# wchasp_v3.net
KiCad netlist of a schematic drawn in EAGLE
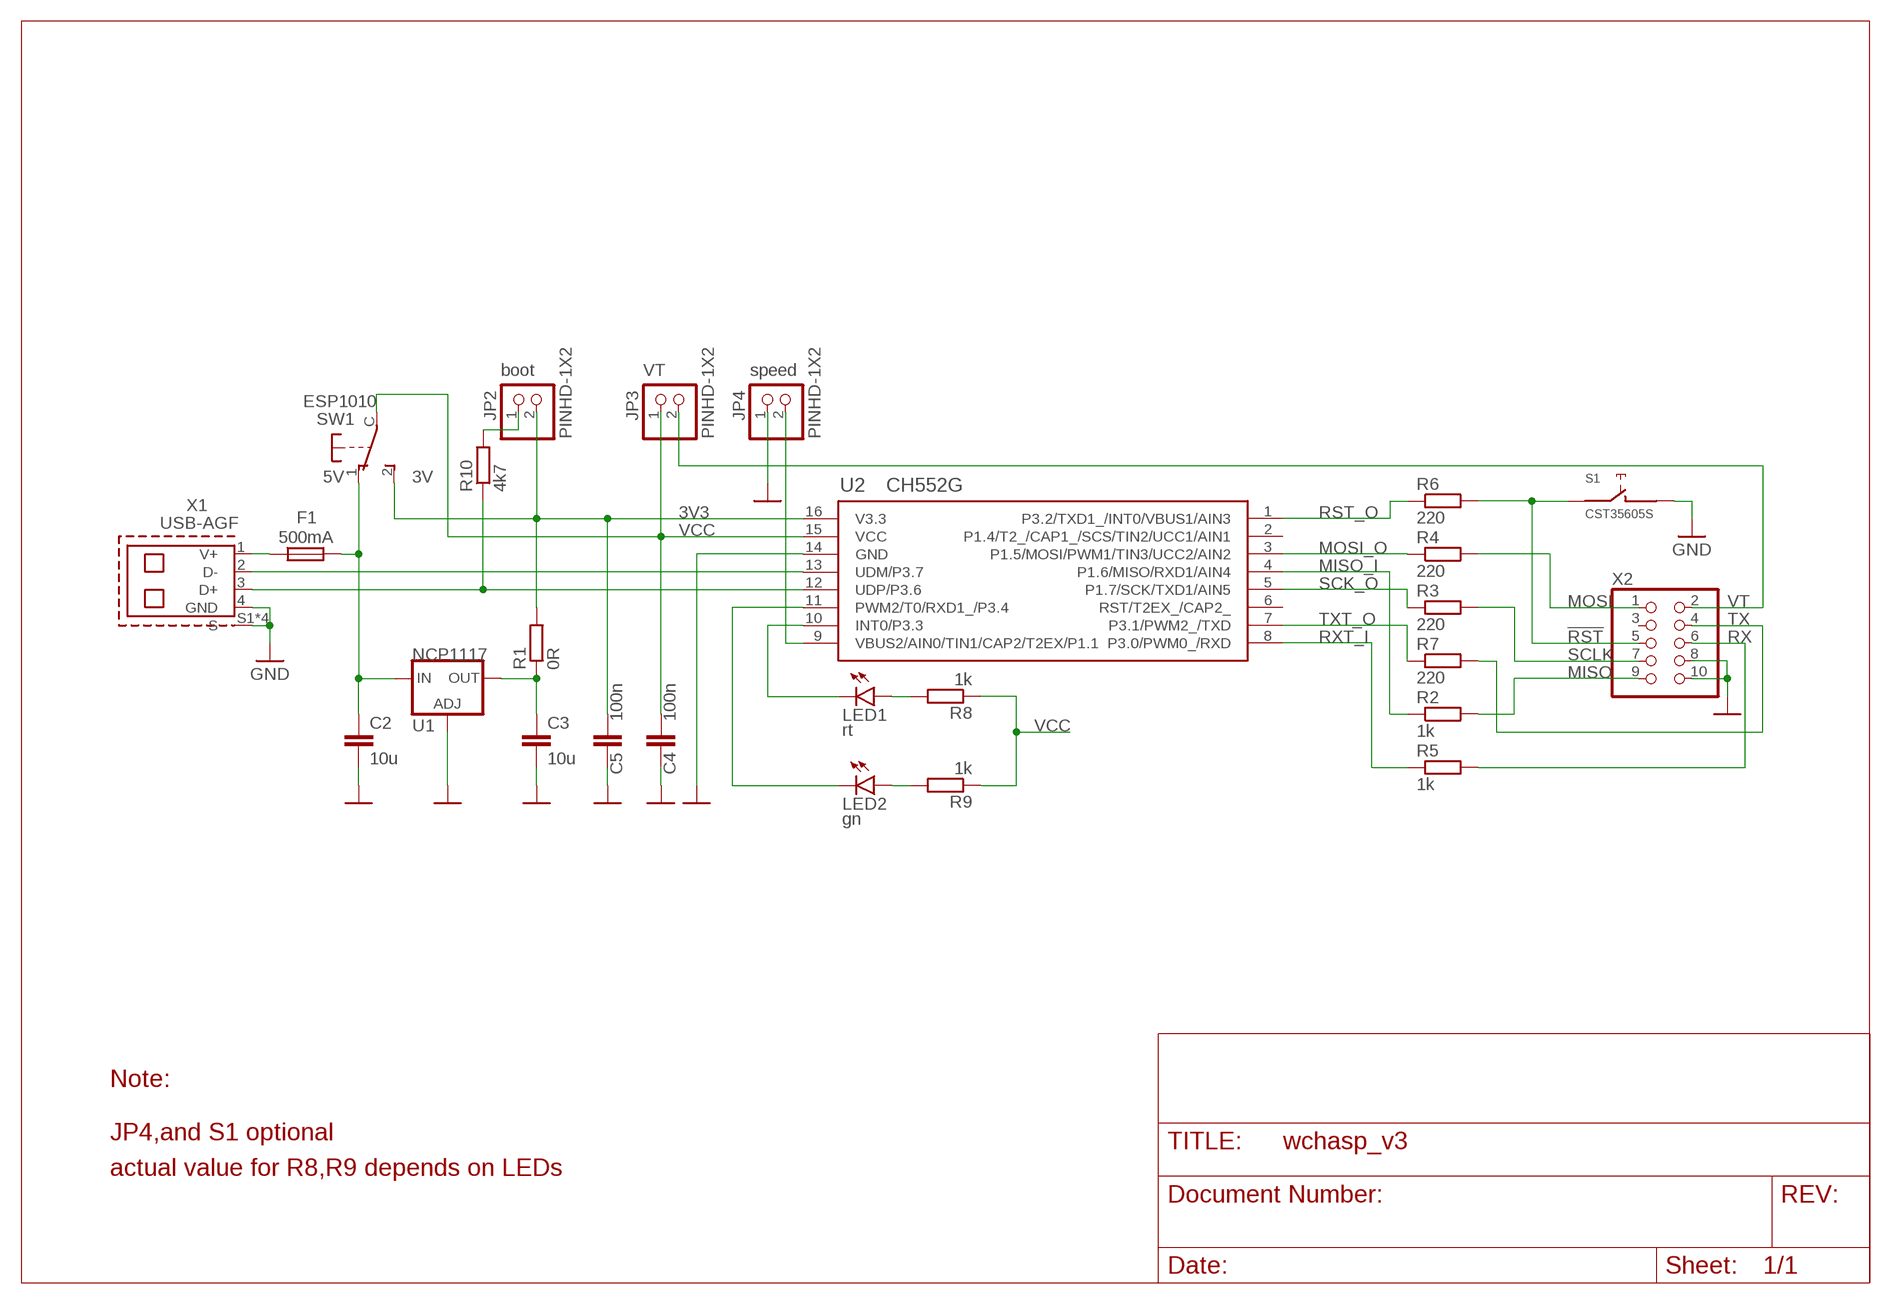
[diagram p0: schematic, sheet 1]

(export (version "E")
  (design (tool "Eeschema 10.0.6"))
  (components
    (comp (ref "C2")
      (value "10u")
      (footprint "eagle-import:C0805K")
      (libsource (lib "eagle-import") (part "C-EUC0805K"))
    )
    (comp (ref "C3")
      (value "10u")
      (footprint "eagle-import:C0805K")
      (libsource (lib "eagle-import") (part "C-EUC0805K"))
    )
    (comp (ref "C4")
      (value "100n")
      (footprint "eagle-import:C0603")
      (libsource (lib "eagle-import") (part "C-EUC0603"))
    )
    (comp (ref "C5")
      (value "100n")
      (footprint "eagle-import:C0603")
      (libsource (lib "eagle-import") (part "C-EUC0603"))
    )
    (comp (ref "F1")
      (value "500mA")
      (footprint "eagle-import:R0805W")
      (libsource (lib "eagle-import") (part "R-EU_R0805W"))
    )
    (comp (ref "JP2")
      (value "PINHD-1X2")
      (footprint "eagle-import:1X2")
      (libsource (lib "eagle-import") (part "PINHD-1X2"))
    )
    (comp (ref "JP3")
      (value "PINHD-1X2")
      (footprint "eagle-import:1X2")
      (libsource (lib "eagle-import") (part "PINHD-1X2"))
    )
    (comp (ref "JP4")
      (value "PINHD-1X2")
      (footprint "eagle-import:1X2")
      (libsource (lib "eagle-import") (part "PINHD-1X2"))
    )
    (comp (ref "LED1")
      (value "rt")
      (footprint "eagle-import:D0603")
      (libsource (lib "eagle-import") (part "LED_0603"))
    )
    (comp (ref "LED2")
      (value "gn")
      (footprint "eagle-import:D0603")
      (libsource (lib "eagle-import") (part "LED_0603"))
    )
    (comp (ref "R1")
      (value "0R")
      (footprint "eagle-import:R0603")
      (libsource (lib "eagle-import") (part "R-EU_R0603"))
    )
    (comp (ref "R2")
      (value "1k")
      (footprint "eagle-import:R0603")
      (libsource (lib "eagle-import") (part "R-EU_R0603"))
    )
    (comp (ref "R3")
      (value "220")
      (footprint "eagle-import:R0603")
      (libsource (lib "eagle-import") (part "R-EU_R0603"))
    )
    (comp (ref "R4")
      (value "220")
      (footprint "eagle-import:R0603")
      (libsource (lib "eagle-import") (part "R-EU_R0603"))
    )
    (comp (ref "R5")
      (value "1k")
      (footprint "eagle-import:R0603")
      (libsource (lib "eagle-import") (part "R-EU_R0603"))
    )
    (comp (ref "R6")
      (value "220")
      (footprint "eagle-import:R0603")
      (libsource (lib "eagle-import") (part "R-EU_R0603"))
    )
    (comp (ref "R7")
      (value "220")
      (footprint "eagle-import:R0603")
      (libsource (lib "eagle-import") (part "R-EU_R0603"))
    )
    (comp (ref "R8")
      (value "1k")
      (footprint "eagle-import:R0603")
      (libsource (lib "eagle-import") (part "R-EU_R0603"))
    )
    (comp (ref "R9")
      (value "1k")
      (footprint "eagle-import:R0603")
      (libsource (lib "eagle-import") (part "R-EU_R0603"))
    )
    (comp (ref "R10")
      (value "4k7")
      (footprint "eagle-import:R0603")
      (libsource (lib "eagle-import") (part "R-EU_R0603"))
    )
    (comp (ref "S1")
      (value "CST35605S")
      (footprint "eagle-import:CST35605S")
      (libsource (lib "eagle-import") (part "CST35605S"))
    )
    (comp (ref "SW1")
      (value "ESP1010")
      (footprint "eagle-import:ESP1010")
      (libsource (lib "eagle-import") (part "ESP1010"))
    )
    (comp (ref "U1")
      (value "NCP1117")
      (footprint "eagle-import:SOT223")
      (libsource (lib "eagle-import") (part "NCP1117"))
    )
    (comp (ref "U2")
      (value "CH552G")
      (footprint "eagle-import:SO16")
      (libsource (lib "eagle-import") (part "CH552G"))
    )
    (comp (ref "X1")
      (value "USB-AGF")
      (footprint "eagle-import:USB-AGF")
      (libsource (lib "eagle-import") (part "USB-AGF"))
    )
    (comp (ref "X2")
      (value "PINHD-2X5/90")
      (footprint "eagle-import:2X05_90")
      (libsource (lib "eagle-import") (part "PINHD-2X5/90"))
    )
  )
  (nets
    (net (code "1") (name "/3V3") (class "Default")
      (node (ref "C5") (pin "1") (pinfunction "1_1") (pintype "passive"))
      (node (ref "JP2") (pin "2") (pinfunction "2_2") (pintype "passive"))
      (node (ref "R1") (pin "2") (pinfunction "2_2") (pintype "passive"))
      (node (ref "SW1") (pin "2") (pinfunction "S_2") (pintype "passive"))
      (node (ref "U2") (pin "16") (pinfunction "V3.3_16") (pintype "output"))
    )
    (net (code "2") (name "/MISO") (class "Default")
      (node (ref "R2") (pin "2") (pinfunction "2_2") (pintype "passive"))
      (node (ref "X2") (pin "9") (pinfunction "9_9") (pintype "passive"))
    )
    (net (code "3") (name "/MISO_I") (class "Default")
      (node (ref "R2") (pin "1") (pinfunction "1_1") (pintype "passive"))
      (node (ref "U2") (pin "4") (pinfunction "P1.6/MISO/RXD1/AIN4_4") (pintype "bidirectional"))
    )
    (net (code "4") (name "/MOSI") (class "Default")
      (node (ref "R4") (pin "2") (pinfunction "2_2") (pintype "passive"))
      (node (ref "X2") (pin "1") (pinfunction "1_1") (pintype "passive"))
    )
    (net (code "5") (name "/MOSI_O") (class "Default")
      (node (ref "R4") (pin "1") (pinfunction "1_1") (pintype "passive"))
      (node (ref "U2") (pin "3") (pinfunction "P1.5/MOSI/PWM1/TIN3/UCC2/AIN2_3") (pintype "bidirectional"))
    )
    (net (code "6") (name "/RST_O") (class "Default")
      (node (ref "R6") (pin "1") (pinfunction "1_1") (pintype "passive"))
      (node (ref "U2") (pin "1") (pinfunction "P3.2/TXD1_/INT0/VBUS1/AIN3_1") (pintype "bidirectional"))
    )
    (net (code "7") (name "/RX") (class "Default")
      (node (ref "R5") (pin "2") (pinfunction "2_2") (pintype "passive"))
      (node (ref "X2") (pin "6") (pinfunction "6_6") (pintype "passive"))
    )
    (net (code "8") (name "/RXT_I") (class "Default")
      (node (ref "R5") (pin "1") (pinfunction "1_1") (pintype "passive"))
      (node (ref "U2") (pin "8") (pinfunction "P3.0/PWM0_/RXD_8") (pintype "bidirectional"))
    )
    (net (code "9") (name "/SCK_O") (class "Default")
      (node (ref "R3") (pin "1") (pinfunction "1_1") (pintype "passive"))
      (node (ref "U2") (pin "5") (pinfunction "P1.7/SCK/TXD1/AIN5_5") (pintype "bidirectional"))
    )
    (net (code "10") (name "/SCLK") (class "Default")
      (node (ref "R3") (pin "2") (pinfunction "2_2") (pintype "passive"))
      (node (ref "X2") (pin "7") (pinfunction "7_7") (pintype "passive"))
    )
    (net (code "11") (name "/TX") (class "Default")
      (node (ref "R7") (pin "2") (pinfunction "2_2") (pintype "passive"))
      (node (ref "X2") (pin "4") (pinfunction "4_4") (pintype "passive"))
    )
    (net (code "12") (name "/TXT_O") (class "Default")
      (node (ref "R7") (pin "1") (pinfunction "1_1") (pintype "passive"))
      (node (ref "U2") (pin "7") (pinfunction "P3.1/PWM2_/TXD_7") (pintype "bidirectional"))
    )
    (net (code "13") (name "/VCC") (class "Default")
      (node (ref "C4") (pin "1") (pinfunction "1_1") (pintype "passive"))
      (node (ref "JP3") (pin "1") (pinfunction "1_1") (pintype "passive"))
      (node (ref "R8") (pin "1") (pinfunction "1_1") (pintype "passive"))
      (node (ref "R9") (pin "1") (pinfunction "1_1") (pintype "passive"))
      (node (ref "SW1") (pin "C") (pinfunction "C_C") (pintype "passive"))
      (node (ref "U2") (pin "15") (pinfunction "VCC_15") (pintype "power_in"))
    )
    (net (code "14") (name "/VT") (class "Default")
      (node (ref "JP3") (pin "2") (pinfunction "2_2") (pintype "passive"))
      (node (ref "X2") (pin "2") (pinfunction "2_2") (pintype "passive"))
    )
    (net (code "15") (name "/~{RST}") (class "Default")
      (node (ref "R6") (pin "2") (pinfunction "2_2") (pintype "passive"))
      (node (ref "S1") (pin "1") (pinfunction "1_1") (pintype "passive"))
      (node (ref "X2") (pin "5") (pinfunction "5_5") (pintype "passive"))
    )
    (net (code "16") (name "GND") (class "Default")
      (node (ref "C2") (pin "2") (pinfunction "2_2") (pintype "passive"))
      (node (ref "C3") (pin "2") (pinfunction "2_2") (pintype "passive"))
      (node (ref "C4") (pin "2") (pinfunction "2_2") (pintype "passive"))
      (node (ref "C5") (pin "2") (pinfunction "2_2") (pintype "passive"))
      (node (ref "JP4") (pin "1") (pinfunction "1_1") (pintype "passive"))
      (node (ref "S1") (pin "2") (pinfunction "2_2") (pintype "passive"))
      (node (ref "U1") (pin "1") (pinfunction "ADJ_1") (pintype "input"))
      (node (ref "U2") (pin "14") (pinfunction "GND_14") (pintype "power_in"))
      (node (ref "X1") (pin "4") (pinfunction "GND_4") (pintype "passive"))
      (node (ref "X1") (pin "S1") (pinfunction "S_S1") (pintype "passive"))
      (node (ref "X1") (pin "S2") (pinfunction "S_S2") (pintype "passive"))
      (node (ref "X1") (pin "S3") (pinfunction "S_S3") (pintype "passive"))
      (node (ref "X1") (pin "S4") (pinfunction "S_S4") (pintype "passive"))
      (node (ref "X2") (pin "10") (pinfunction "10_10") (pintype "passive"))
      (node (ref "X2") (pin "8") (pinfunction "8_8") (pintype "passive"))
    )
    (net (code "17") (name "Net-(C3-Pad1)") (class "Default")
      (node (ref "C3") (pin "1") (pinfunction "1_1") (pintype "passive"))
      (node (ref "R1") (pin "1") (pinfunction "1_1") (pintype "passive"))
      (node (ref "U1") (pin "2") (pinfunction "OUT_2") (pintype "passive"))
      (node (ref "U1") (pin "4") (pinfunction "OUT_4") (pintype "passive"))
    )
    (net (code "18") (name "Net-(JP2-Pad1)") (class "Default")
      (node (ref "JP2") (pin "1") (pinfunction "1_1") (pintype "passive"))
      (node (ref "R10") (pin "2") (pinfunction "2_2") (pintype "passive"))
    )
    (net (code "19") (name "Net-(LED1-C)") (class "Default")
      (node (ref "LED1") (pin "K") (pinfunction "C_K") (pintype "passive"))
      (node (ref "U2") (pin "10") (pinfunction "INT0/P3.3_10") (pintype "bidirectional"))
    )
    (net (code "20") (name "Net-(LED1-PadA)") (class "Default")
      (node (ref "LED1") (pin "A") (pinfunction "A_A") (pintype "passive"))
      (node (ref "R8") (pin "2") (pinfunction "2_2") (pintype "passive"))
    )
    (net (code "21") (name "Net-(LED2-C)") (class "Default")
      (node (ref "LED2") (pin "K") (pinfunction "C_K") (pintype "passive"))
      (node (ref "U2") (pin "11") (pinfunction "PWM2/T0/RXD1_/P3.4_11") (pintype "bidirectional"))
    )
    (net (code "22") (name "Net-(LED2-PadA)") (class "Default")
      (node (ref "LED2") (pin "A") (pinfunction "A_A") (pintype "passive"))
      (node (ref "R9") (pin "2") (pinfunction "2_2") (pintype "passive"))
    )
    (net (code "23") (name "Net-(SW1-O)") (class "Default")
      (node (ref "C2") (pin "1") (pinfunction "1_1") (pintype "passive"))
      (node (ref "F1") (pin "2") (pinfunction "2_2") (pintype "passive"))
      (node (ref "SW1") (pin "1") (pinfunction "O_1") (pintype "passive"))
      (node (ref "U1") (pin "3") (pinfunction "IN_3") (pintype "input"))
    )
    (net (code "24") (name "Net-(U2-UDM{slash}P3.7)") (class "Default")
      (node (ref "U2") (pin "13") (pinfunction "UDM/P3.7_13") (pintype "bidirectional"))
      (node (ref "X1") (pin "2") (pinfunction "D-_2") (pintype "passive"))
    )
    (net (code "25") (name "Net-(U2-UDP{slash}P3.6)") (class "Default")
      (node (ref "R10") (pin "1") (pinfunction "1_1") (pintype "passive"))
      (node (ref "U2") (pin "12") (pinfunction "UDP/P3.6_12") (pintype "bidirectional"))
      (node (ref "X1") (pin "3") (pinfunction "D+_3") (pintype "passive"))
    )
    (net (code "26") (name "Net-(U2-VBUS2{slash}AIN0{slash}TIN1{slash}CAP2{slash}T2EX{slash}P1.1)") (class "Default")
      (node (ref "JP4") (pin "2") (pinfunction "2_2") (pintype "passive"))
      (node (ref "U2") (pin "9") (pinfunction "VBUS2/AIN0/TIN1/CAP2/T2EX/P1.1_9") (pintype "bidirectional"))
    )
    (net (code "27") (name "Net-(X1-V+)") (class "Default")
      (node (ref "F1") (pin "1") (pinfunction "1_1") (pintype "passive"))
      (node (ref "X1") (pin "1") (pinfunction "V+_1") (pintype "passive"))
    )
    (net (code "28") (name "unconnected-(U2-P1.4{slash}T2_{slash}CAP1_{slash}SCS{slash}TIN2{slash}UCC1{slash}AIN1-Pad2)") (class "Default")
      (node (ref "U2") (pin "2") (pinfunction "P1.4/T2_/CAP1_/SCS/TIN2/UCC1/AIN1_2") (pintype "bidirectional"))
    )
    (net (code "29") (name "unconnected-(U2-RST{slash}T2EX_{slash}CAP2_-Pad6)") (class "Default")
      (node (ref "U2") (pin "6") (pinfunction "RST/T2EX_/CAP2__6") (pintype "bidirectional"))
    )
    (net (code "30") (name "unconnected-(X2-Pad3)") (class "Default")
      (node (ref "X2") (pin "3") (pinfunction "3_3") (pintype "passive"))
    )
  )
)
